# MC_Connector.net
KiCad netlist of a schematic drawn in Altium Designer
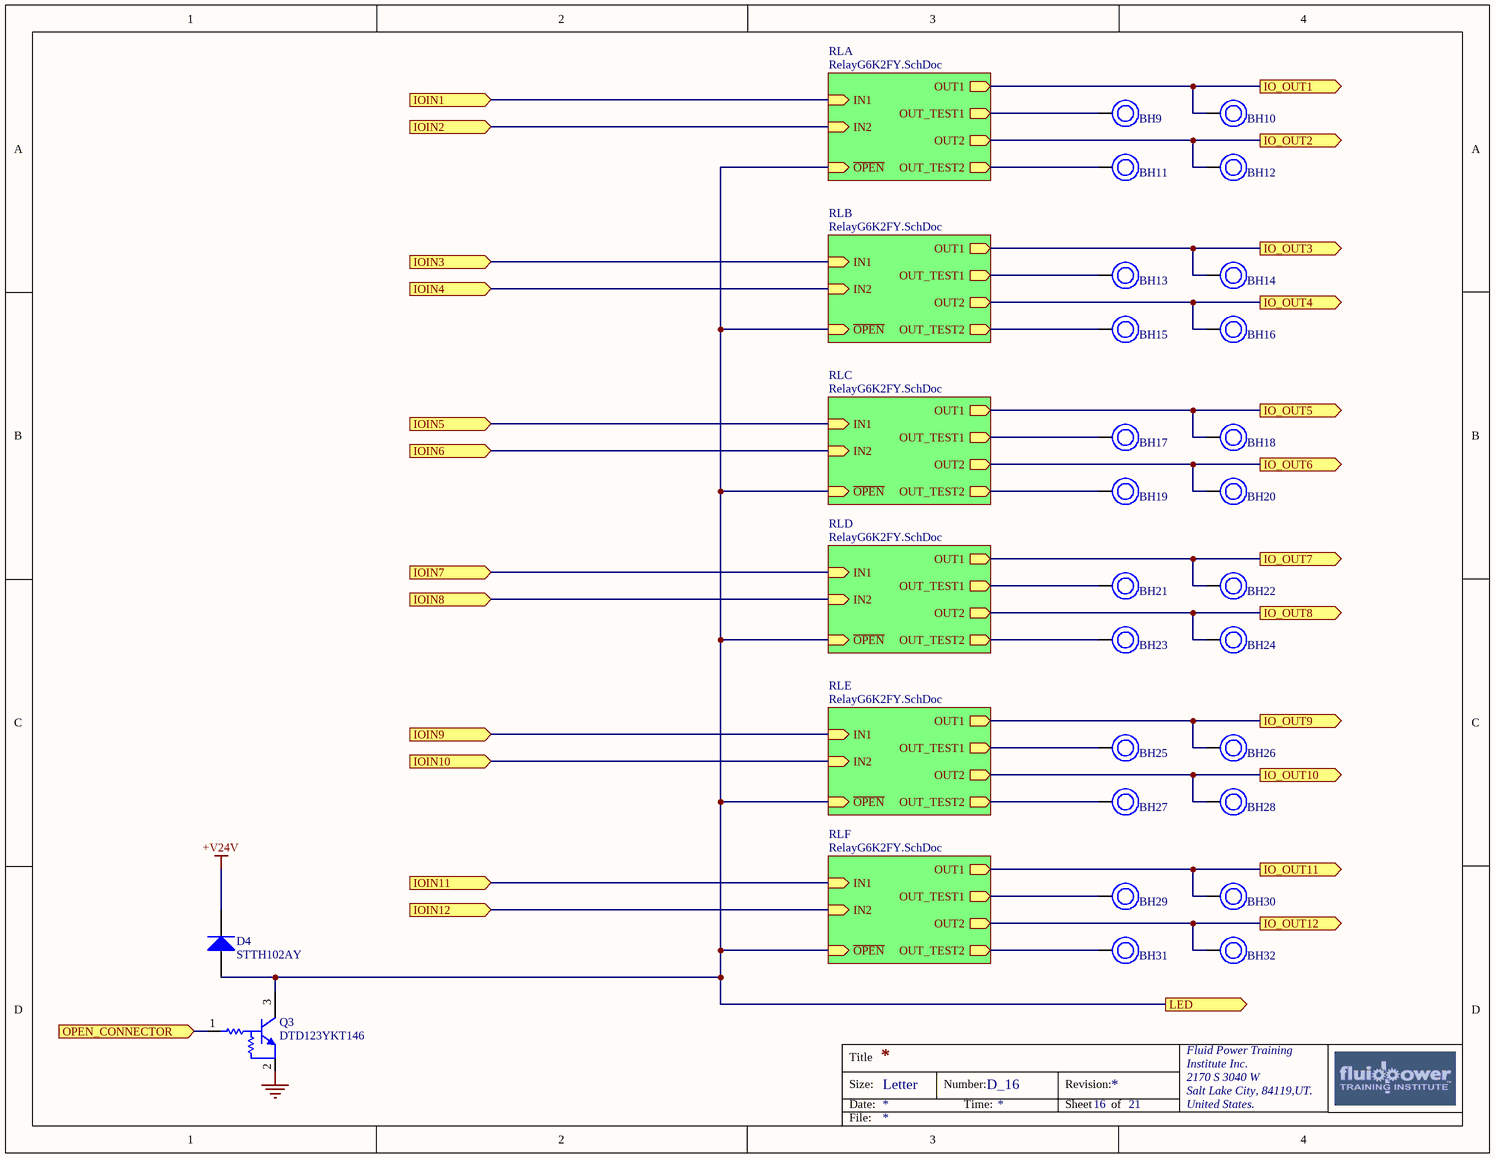
[diagram p0: MC_Connector.SchDoc]

(export (version "E")
  (design (tool "Eeschema 10.0.6"))
  (components
    (comp (ref "BH9")
      (value "BananaHole")
      (footprint "MC1:BananaHole")
      (description "Banana hole for panel testing and board mounting")
      (libsource (lib "MC1") (part "BananaHole"))
    )
    (comp (ref "BH10")
      (value "BananaHole")
      (footprint "MC1:BananaHole")
      (description "Banana hole for panel testing and board mounting")
      (libsource (lib "MC1") (part "BananaHole"))
    )
    (comp (ref "BH11")
      (value "BananaHole")
      (footprint "MC1:BananaHole")
      (description "Banana hole for panel testing and board mounting")
      (libsource (lib "MC1") (part "BananaHole"))
    )
    (comp (ref "BH12")
      (value "BananaHole")
      (footprint "MC1:BananaHole")
      (description "Banana hole for panel testing and board mounting")
      (libsource (lib "MC1") (part "BananaHole"))
    )
    (comp (ref "BH13")
      (value "BananaHole")
      (footprint "MC1:BananaHole")
      (description "Banana hole for panel testing and board mounting")
      (libsource (lib "MC1") (part "BananaHole"))
    )
    (comp (ref "BH14")
      (value "BananaHole")
      (footprint "MC1:BananaHole")
      (description "Banana hole for panel testing and board mounting")
      (libsource (lib "MC1") (part "BananaHole"))
    )
    (comp (ref "BH15")
      (value "BananaHole")
      (footprint "MC1:BananaHole")
      (description "Banana hole for panel testing and board mounting")
      (libsource (lib "MC1") (part "BananaHole"))
    )
    (comp (ref "BH16")
      (value "BananaHole")
      (footprint "MC1:BananaHole")
      (description "Banana hole for panel testing and board mounting")
      (libsource (lib "MC1") (part "BananaHole"))
    )
    (comp (ref "BH17")
      (value "BananaHole")
      (footprint "MC1:BananaHole")
      (description "Banana hole for panel testing and board mounting")
      (libsource (lib "MC1") (part "BananaHole"))
    )
    (comp (ref "BH18")
      (value "BananaHole")
      (footprint "MC1:BananaHole")
      (description "Banana hole for panel testing and board mounting")
      (libsource (lib "MC1") (part "BananaHole"))
    )
    (comp (ref "BH19")
      (value "BananaHole")
      (footprint "MC1:BananaHole")
      (description "Banana hole for panel testing and board mounting")
      (libsource (lib "MC1") (part "BananaHole"))
    )
    (comp (ref "BH20")
      (value "BananaHole")
      (footprint "MC1:BananaHole")
      (description "Banana hole for panel testing and board mounting")
      (libsource (lib "MC1") (part "BananaHole"))
    )
    (comp (ref "BH21")
      (value "BananaHole")
      (footprint "MC1:BananaHole")
      (description "Banana hole for panel testing and board mounting")
      (libsource (lib "MC1") (part "BananaHole"))
    )
    (comp (ref "BH22")
      (value "BananaHole")
      (footprint "MC1:BananaHole")
      (description "Banana hole for panel testing and board mounting")
      (libsource (lib "MC1") (part "BananaHole"))
    )
    (comp (ref "BH23")
      (value "BananaHole")
      (footprint "MC1:BananaHole")
      (description "Banana hole for panel testing and board mounting")
      (libsource (lib "MC1") (part "BananaHole"))
    )
    (comp (ref "BH24")
      (value "BananaHole")
      (footprint "MC1:BananaHole")
      (description "Banana hole for panel testing and board mounting")
      (libsource (lib "MC1") (part "BananaHole"))
    )
    (comp (ref "BH25")
      (value "BananaHole")
      (footprint "MC1:BananaHole")
      (description "Banana hole for panel testing and board mounting")
      (libsource (lib "MC1") (part "BananaHole"))
    )
    (comp (ref "BH26")
      (value "BananaHole")
      (footprint "MC1:BananaHole")
      (description "Banana hole for panel testing and board mounting")
      (libsource (lib "MC1") (part "BananaHole"))
    )
    (comp (ref "BH27")
      (value "BananaHole")
      (footprint "MC1:BananaHole")
      (description "Banana hole for panel testing and board mounting")
      (libsource (lib "MC1") (part "BananaHole"))
    )
    (comp (ref "BH28")
      (value "BananaHole")
      (footprint "MC1:BananaHole")
      (description "Banana hole for panel testing and board mounting")
      (libsource (lib "MC1") (part "BananaHole"))
    )
    (comp (ref "BH29")
      (value "BananaHole")
      (footprint "MC1:BananaHole")
      (description "Banana hole for panel testing and board mounting")
      (libsource (lib "MC1") (part "BananaHole"))
    )
    (comp (ref "BH30")
      (value "BananaHole")
      (footprint "MC1:BananaHole")
      (description "Banana hole for panel testing and board mounting")
      (libsource (lib "MC1") (part "BananaHole"))
    )
    (comp (ref "BH31")
      (value "BananaHole")
      (footprint "MC1:BananaHole")
      (description "Banana hole for panel testing and board mounting")
      (libsource (lib "MC1") (part "BananaHole"))
    )
    (comp (ref "BH32")
      (value "BananaHole")
      (footprint "MC1:BananaHole")
      (description "Banana hole for panel testing and board mounting")
      (libsource (lib "MC1") (part "BananaHole"))
    )
    (comp (ref "D4")
      (value "STTH102AY")
      (footprint "MC1:DIOM4326X26M")
      (description "DIODE GEN PURP 200V 1A SMA")
      (fields (field (name "MANUFACTURER") "STMicroelectronics"))
      (libsource (lib "MC1") (part "STTH102AY"))
    )
    (comp (ref "Q3")
      (value "DTD123YKT146")
      (footprint "MC1:SOT95P280X130-3N")
      (description "TRANS PREBIAS NPN 200MW SMT3")
      (fields (field (name "MANUFACTURER") "Rohm"))
      (libsource (lib "MC1") (part "DTD123YKT146"))
    )
  )
  (nets
    (net (code "1") (name "+V24V") (class "Default")
      (node (ref "D4") (pin "1") (pinfunction "K_1") (pintype "passive"))
    )
    (net (code "14") (name "/IO_OUT1") (class "Default")
      (node (ref "BH10") (pin "1") (pinfunction "1_1") (pintype "passive"))
    )
    (net (code "15") (name "/IO_OUT2") (class "Default")
      (node (ref "BH12") (pin "1") (pinfunction "1_1") (pintype "passive"))
    )
    (net (code "16") (name "/IO_OUT3") (class "Default")
      (node (ref "BH14") (pin "1") (pinfunction "1_1") (pintype "passive"))
    )
    (net (code "17") (name "/IO_OUT4") (class "Default")
      (node (ref "BH16") (pin "1") (pinfunction "1_1") (pintype "passive"))
    )
    (net (code "18") (name "/IO_OUT5") (class "Default")
      (node (ref "BH18") (pin "1") (pinfunction "1_1") (pintype "passive"))
    )
    (net (code "19") (name "/IO_OUT6") (class "Default")
      (node (ref "BH20") (pin "1") (pinfunction "1_1") (pintype "passive"))
    )
    (net (code "20") (name "/IO_OUT7") (class "Default")
      (node (ref "BH22") (pin "1") (pinfunction "1_1") (pintype "passive"))
    )
    (net (code "21") (name "/IO_OUT8") (class "Default")
      (node (ref "BH24") (pin "1") (pinfunction "1_1") (pintype "passive"))
    )
    (net (code "22") (name "/IO_OUT9") (class "Default")
      (node (ref "BH26") (pin "1") (pinfunction "1_1") (pintype "passive"))
    )
    (net (code "23") (name "/IO_OUT10") (class "Default")
      (node (ref "BH28") (pin "1") (pinfunction "1_1") (pintype "passive"))
    )
    (net (code "24") (name "/IO_OUT11") (class "Default")
      (node (ref "BH30") (pin "1") (pinfunction "1_1") (pintype "passive"))
    )
    (net (code "25") (name "/IO_OUT12") (class "Default")
      (node (ref "BH32") (pin "1") (pinfunction "1_1") (pintype "passive"))
    )
    (net (code "26") (name "/LED") (class "Default")
      (node (ref "D4") (pin "2") (pinfunction "A_2") (pintype "passive"))
      (node (ref "Q3") (pin "3") (pinfunction "C_3") (pintype "passive"))
    )
    (net (code "27") (name "/OPEN_CONNECTOR") (class "Default")
      (node (ref "Q3") (pin "1") (pinfunction "B_1") (pintype "passive"))
    )
    (net (code "28") (name "/OUT_TEST1") (class "Default")
      (node (ref "BH13") (pin "1") (pinfunction "1_1") (pintype "passive"))
    )
    (net (code "29") (name "/OUT_TEST1_1") (class "Default")
      (node (ref "BH21") (pin "1") (pinfunction "1_1") (pintype "passive"))
    )
    (net (code "30") (name "/OUT_TEST1_2") (class "Default")
      (node (ref "BH25") (pin "1") (pinfunction "1_1") (pintype "passive"))
    )
    (net (code "31") (name "/OUT_TEST1_3") (class "Default")
      (node (ref "BH29") (pin "1") (pinfunction "1_1") (pintype "passive"))
    )
    (net (code "32") (name "/OUT_TEST1_4") (class "Default")
      (node (ref "BH17") (pin "1") (pinfunction "1_1") (pintype "passive"))
    )
    (net (code "33") (name "/OUT_TEST1_5") (class "Default")
      (node (ref "BH9") (pin "1") (pinfunction "1_1") (pintype "passive"))
    )
    (net (code "34") (name "/OUT_TEST2") (class "Default")
      (node (ref "BH15") (pin "1") (pinfunction "1_1") (pintype "passive"))
    )
    (net (code "35") (name "/OUT_TEST2_1") (class "Default")
      (node (ref "BH23") (pin "1") (pinfunction "1_1") (pintype "passive"))
    )
    (net (code "36") (name "/OUT_TEST2_2") (class "Default")
      (node (ref "BH27") (pin "1") (pinfunction "1_1") (pintype "passive"))
    )
    (net (code "37") (name "/OUT_TEST2_3") (class "Default")
      (node (ref "BH31") (pin "1") (pinfunction "1_1") (pintype "passive"))
    )
    (net (code "38") (name "/OUT_TEST2_4") (class "Default")
      (node (ref "BH19") (pin "1") (pinfunction "1_1") (pintype "passive"))
    )
    (net (code "39") (name "/OUT_TEST2_5") (class "Default")
      (node (ref "BH11") (pin "1") (pinfunction "1_1") (pintype "passive"))
    )
    (net (code "40") (name "GND") (class "Default")
      (node (ref "Q3") (pin "2") (pinfunction "E_2") (pintype "passive"))
    )
  )
)
